# Tranzistory_jako_spina_e.net
KiCad netlist of a schematic drawn in Altium Designer
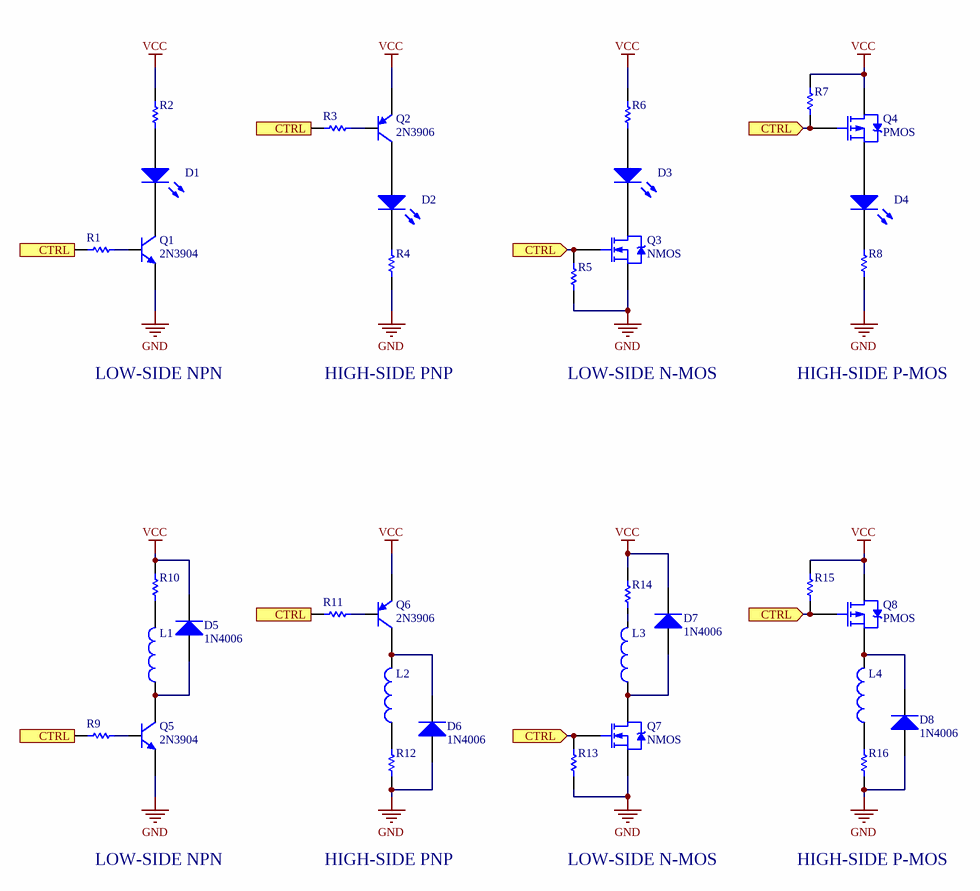
[diagram p0: Tranzistory jako spinače.SchDoc]

(export (version "E")
  (design (tool "Eeschema 10.0.6"))
  (components
    (comp (ref "D1")
      (value "LED0")
      (footprint "LED-0")
      (description "Typical INFRARED GaAs LED")
      (fields (field (name "PUBLISHER") "Altium Limited"))
      (libsource (lib "Miscellaneous Devices") (part "LED0"))
    )
    (comp (ref "D2")
      (value "LED0")
      (footprint "LED-0")
      (description "Typical INFRARED GaAs LED")
      (fields (field (name "PUBLISHER") "Altium Limited"))
      (libsource (lib "Miscellaneous Devices") (part "LED0"))
    )
    (comp (ref "D3")
      (value "LED0")
      (footprint "LED-0")
      (description "Typical INFRARED GaAs LED")
      (fields (field (name "PUBLISHER") "Altium Limited"))
      (libsource (lib "Miscellaneous Devices") (part "LED0"))
    )
    (comp (ref "D4")
      (value "LED0")
      (footprint "LED-0")
      (description "Typical INFRARED GaAs LED")
      (fields (field (name "PUBLISHER") "Altium Limited"))
      (libsource (lib "Miscellaneous Devices") (part "LED0"))
    )
    (comp (ref "D5")
      (value "1N4006")
      (footprint "DO-41")
      (description "1 Amp General Purpose Rectifier")
      (fields (field (name "PUBLISHER") "Altium Limited"))
      (libsource (lib "Miscellaneous Devices") (part "Diode 1N4006"))
    )
    (comp (ref "D6")
      (value "1N4006")
      (footprint "DO-41")
      (description "1 Amp General Purpose Rectifier")
      (fields (field (name "PUBLISHER") "Altium Limited"))
      (libsource (lib "Miscellaneous Devices") (part "Diode 1N4006"))
    )
    (comp (ref "D7")
      (value "1N4006")
      (footprint "DO-41")
      (description "1 Amp General Purpose Rectifier")
      (fields (field (name "PUBLISHER") "Altium Limited"))
      (libsource (lib "Miscellaneous Devices") (part "Diode 1N4006"))
    )
    (comp (ref "D8")
      (value "1N4006")
      (footprint "DO-41")
      (description "1 Amp General Purpose Rectifier")
      (fields (field (name "PUBLISHER") "Altium Limited"))
      (libsource (lib "Miscellaneous Devices") (part "Diode 1N4006"))
    )
    (comp (ref "L1")
      (value "Inductor")
      (footprint "0402-A")
      (fields (field (name "PUBLISHER") "Altium Limited"))
      (libsource (lib "Miscellaneous Devices") (part "Inductor"))
    )
    (comp (ref "L2")
      (value "Inductor")
      (footprint "0402-A")
      (fields (field (name "PUBLISHER") "Altium Limited"))
      (libsource (lib "Miscellaneous Devices") (part "Inductor"))
    )
    (comp (ref "L3")
      (value "Inductor")
      (footprint "0402-A")
      (fields (field (name "PUBLISHER") "Altium Limited"))
      (libsource (lib "Miscellaneous Devices") (part "Inductor"))
    )
    (comp (ref "L4")
      (value "Inductor")
      (footprint "0402-A")
      (fields (field (name "PUBLISHER") "Altium Limited"))
      (libsource (lib "Miscellaneous Devices") (part "Inductor"))
    )
    (comp (ref "Q1")
      (value "2N3904")
      (footprint "TO-92A")
      (description "NPN General Purpose Amplifier")
      (fields (field (name "PUBLISHER") "Altium Limited"))
      (libsource (lib "Miscellaneous Devices") (part "2N3904"))
    )
    (comp (ref "Q2")
      (value "2N3906")
      (footprint "TO-92A")
      (description "PNP General Purpose Amplifier")
      (fields (field (name "PUBLISHER") "Altium Limited"))
      (libsource (lib "Miscellaneous Devices") (part "2N3906"))
    )
    (comp (ref "Q3")
      (value "NMOS")
      (footprint "TO-220AB")
      (description "N-Channel Power MOSFET")
      (fields (field (name "PUBLISHER") "Altium Limited"))
      (libsource (lib "Miscellaneous Devices") (part "NMOS-2"))
    )
    (comp (ref "Q4")
      (value "PMOS")
      (footprint "TO-220AB")
      (description "P-Channel Power MOSFET")
      (fields (field (name "PUBLISHER") "Altium Limited"))
      (libsource (lib "Miscellaneous Devices") (part "PMOS-2"))
    )
    (comp (ref "Q5")
      (value "2N3904")
      (footprint "TO-92A")
      (description "NPN General Purpose Amplifier")
      (fields (field (name "PUBLISHER") "Altium Limited"))
      (libsource (lib "Miscellaneous Devices") (part "2N3904"))
    )
    (comp (ref "Q6")
      (value "2N3906")
      (footprint "TO-92A")
      (description "PNP General Purpose Amplifier")
      (fields (field (name "PUBLISHER") "Altium Limited"))
      (libsource (lib "Miscellaneous Devices") (part "2N3906"))
    )
    (comp (ref "Q7")
      (value "NMOS")
      (footprint "TO-220AB")
      (description "N-Channel Power MOSFET")
      (fields (field (name "PUBLISHER") "Altium Limited"))
      (libsource (lib "Miscellaneous Devices") (part "NMOS-2"))
    )
    (comp (ref "Q8")
      (value "PMOS")
      (footprint "TO-220AB")
      (description "P-Channel Power MOSFET")
      (fields (field (name "PUBLISHER") "Altium Limited"))
      (libsource (lib "Miscellaneous Devices") (part "PMOS-2"))
    )
    (comp (ref "R1")
      (value "Res1")
      (footprint "AXIAL-0.3")
      (description "Resistor")
      (fields (field (name "PUBLISHER") "Altium Limited"))
      (libsource (lib "Miscellaneous Devices") (part "Res1"))
    )
    (comp (ref "R2")
      (value "Res1")
      (footprint "AXIAL-0.3")
      (description "Resistor")
      (fields (field (name "PUBLISHER") "Altium Limited"))
      (libsource (lib "Miscellaneous Devices") (part "Res1"))
    )
    (comp (ref "R3")
      (value "Res1")
      (footprint "AXIAL-0.3")
      (description "Resistor")
      (fields (field (name "PUBLISHER") "Altium Limited"))
      (libsource (lib "Miscellaneous Devices") (part "Res1"))
    )
    (comp (ref "R4")
      (value "Res1")
      (footprint "AXIAL-0.3")
      (description "Resistor")
      (fields (field (name "PUBLISHER") "Altium Limited"))
      (libsource (lib "Miscellaneous Devices") (part "Res1"))
    )
    (comp (ref "R5")
      (value "Res1")
      (footprint "AXIAL-0.3")
      (description "Resistor")
      (fields (field (name "PUBLISHER") "Altium Limited"))
      (libsource (lib "Miscellaneous Devices") (part "Res1"))
    )
    (comp (ref "R6")
      (value "Res1")
      (footprint "AXIAL-0.3")
      (description "Resistor")
      (fields (field (name "PUBLISHER") "Altium Limited"))
      (libsource (lib "Miscellaneous Devices") (part "Res1"))
    )
    (comp (ref "R7")
      (value "Res1")
      (footprint "AXIAL-0.3")
      (description "Resistor")
      (fields (field (name "PUBLISHER") "Altium Limited"))
      (libsource (lib "Miscellaneous Devices") (part "Res1"))
    )
    (comp (ref "R8")
      (value "Res1")
      (footprint "AXIAL-0.3")
      (description "Resistor")
      (fields (field (name "PUBLISHER") "Altium Limited"))
      (libsource (lib "Miscellaneous Devices") (part "Res1"))
    )
    (comp (ref "R9")
      (value "Res1")
      (footprint "AXIAL-0.3")
      (description "Resistor")
      (fields (field (name "PUBLISHER") "Altium Limited"))
      (libsource (lib "Miscellaneous Devices") (part "Res1"))
    )
    (comp (ref "R10")
      (value "Res1")
      (footprint "AXIAL-0.3")
      (description "Resistor")
      (fields (field (name "PUBLISHER") "Altium Limited"))
      (libsource (lib "Miscellaneous Devices") (part "Res1"))
    )
    (comp (ref "R11")
      (value "Res1")
      (footprint "AXIAL-0.3")
      (description "Resistor")
      (fields (field (name "PUBLISHER") "Altium Limited"))
      (libsource (lib "Miscellaneous Devices") (part "Res1"))
    )
    (comp (ref "R12")
      (value "Res1")
      (footprint "AXIAL-0.3")
      (description "Resistor")
      (fields (field (name "PUBLISHER") "Altium Limited"))
      (libsource (lib "Miscellaneous Devices") (part "Res1"))
    )
    (comp (ref "R13")
      (value "Res1")
      (footprint "AXIAL-0.3")
      (description "Resistor")
      (fields (field (name "PUBLISHER") "Altium Limited"))
      (libsource (lib "Miscellaneous Devices") (part "Res1"))
    )
    (comp (ref "R14")
      (value "Res1")
      (footprint "AXIAL-0.3")
      (description "Resistor")
      (fields (field (name "PUBLISHER") "Altium Limited"))
      (libsource (lib "Miscellaneous Devices") (part "Res1"))
    )
    (comp (ref "R15")
      (value "Res1")
      (footprint "AXIAL-0.3")
      (description "Resistor")
      (fields (field (name "PUBLISHER") "Altium Limited"))
      (libsource (lib "Miscellaneous Devices") (part "Res1"))
    )
    (comp (ref "R16")
      (value "Res1")
      (footprint "AXIAL-0.3")
      (description "Resistor")
      (fields (field (name "PUBLISHER") "Altium Limited"))
      (libsource (lib "Miscellaneous Devices") (part "Res1"))
    )
  )
  (nets
    (net (code "1") (name "/CTRL") (class "Default")
      (node (ref "Q3") (pin "1") (pinfunction "G_1") (pintype "passive"))
      (node (ref "Q4") (pin "1") (pinfunction "G_1") (pintype "passive"))
      (node (ref "Q7") (pin "1") (pinfunction "G_1") (pintype "passive"))
      (node (ref "Q8") (pin "1") (pinfunction "G_1") (pintype "passive"))
      (node (ref "R1") (pin "2") (pinfunction "2_2") (pintype "passive"))
      (node (ref "R11") (pin "2") (pinfunction "2_2") (pintype "passive"))
      (node (ref "R13") (pin "1") (pinfunction "1_1") (pintype "passive"))
      (node (ref "R15") (pin "2") (pinfunction "2_2") (pintype "passive"))
      (node (ref "R3") (pin "2") (pinfunction "2_2") (pintype "passive"))
      (node (ref "R5") (pin "1") (pinfunction "1_1") (pintype "passive"))
      (node (ref "R7") (pin "2") (pinfunction "2_2") (pintype "passive"))
      (node (ref "R9") (pin "2") (pinfunction "2_2") (pintype "passive"))
    )
    (net (code "2") (name "GND") (class "Default")
      (node (ref "D6") (pin "1") (pinfunction "A_1") (pintype "passive"))
      (node (ref "D8") (pin "1") (pinfunction "A_1") (pintype "passive"))
      (node (ref "Q1") (pin "1") (pinfunction "E_1") (pintype "passive"))
      (node (ref "Q3") (pin "3") (pinfunction "S_3") (pintype "passive"))
      (node (ref "Q5") (pin "1") (pinfunction "E_1") (pintype "passive"))
      (node (ref "Q7") (pin "3") (pinfunction "S_3") (pintype "passive"))
      (node (ref "R12") (pin "1") (pinfunction "1_1") (pintype "passive"))
      (node (ref "R13") (pin "2") (pinfunction "2_2") (pintype "passive"))
      (node (ref "R16") (pin "1") (pinfunction "1_1") (pintype "passive"))
      (node (ref "R4") (pin "1") (pinfunction "1_1") (pintype "passive"))
      (node (ref "R5") (pin "2") (pinfunction "2_2") (pintype "passive"))
      (node (ref "R8") (pin "1") (pinfunction "1_1") (pintype "passive"))
    )
    (net (code "3") (name "Net-(D1-A)") (class "Default")
      (node (ref "D1") (pin "1") (pinfunction "A_1") (pintype "passive"))
      (node (ref "R2") (pin "1") (pinfunction "1_1") (pintype "passive"))
    )
    (net (code "4") (name "Net-(D1-K)") (class "Default")
      (node (ref "D1") (pin "2") (pinfunction "K_2") (pintype "passive"))
      (node (ref "Q1") (pin "3") (pinfunction "C_3") (pintype "passive"))
    )
    (net (code "5") (name "Net-(D2-A)") (class "Default")
      (node (ref "D2") (pin "1") (pinfunction "A_1") (pintype "passive"))
      (node (ref "Q2") (pin "3") (pinfunction "C_3") (pintype "passive"))
    )
    (net (code "6") (name "Net-(D2-K)") (class "Default")
      (node (ref "D2") (pin "2") (pinfunction "K_2") (pintype "passive"))
      (node (ref "R4") (pin "2") (pinfunction "2_2") (pintype "passive"))
    )
    (net (code "7") (name "Net-(D3-A)") (class "Default")
      (node (ref "D3") (pin "1") (pinfunction "A_1") (pintype "passive"))
      (node (ref "R6") (pin "1") (pinfunction "1_1") (pintype "passive"))
    )
    (net (code "8") (name "Net-(D3-K)") (class "Default")
      (node (ref "D3") (pin "2") (pinfunction "K_2") (pintype "passive"))
      (node (ref "Q3") (pin "2") (pinfunction "D_2") (pintype "passive"))
    )
    (net (code "9") (name "Net-(D4-A)") (class "Default")
      (node (ref "D4") (pin "1") (pinfunction "A_1") (pintype "passive"))
      (node (ref "Q4") (pin "3") (pinfunction "S_3") (pintype "passive"))
    )
    (net (code "10") (name "Net-(D4-K)") (class "Default")
      (node (ref "D4") (pin "2") (pinfunction "K_2") (pintype "passive"))
      (node (ref "R8") (pin "2") (pinfunction "2_2") (pintype "passive"))
    )
    (net (code "11") (name "Net-(D5-A)") (class "Default")
      (node (ref "D5") (pin "1") (pinfunction "A_1") (pintype "passive"))
      (node (ref "L1") (pin "1") (pinfunction "1_1") (pintype "passive"))
      (node (ref "Q5") (pin "3") (pinfunction "C_3") (pintype "passive"))
    )
    (net (code "12") (name "Net-(D6-K)") (class "Default")
      (node (ref "D6") (pin "2") (pinfunction "K_2") (pintype "passive"))
      (node (ref "L2") (pin "2") (pinfunction "2_2") (pintype "passive"))
      (node (ref "Q6") (pin "3") (pinfunction "C_3") (pintype "passive"))
    )
    (net (code "13") (name "Net-(D7-A)") (class "Default")
      (node (ref "D7") (pin "1") (pinfunction "A_1") (pintype "passive"))
      (node (ref "L3") (pin "1") (pinfunction "1_1") (pintype "passive"))
      (node (ref "Q7") (pin "2") (pinfunction "D_2") (pintype "passive"))
    )
    (net (code "14") (name "Net-(D8-K)") (class "Default")
      (node (ref "D8") (pin "2") (pinfunction "K_2") (pintype "passive"))
      (node (ref "L4") (pin "2") (pinfunction "2_2") (pintype "passive"))
      (node (ref "Q8") (pin "3") (pinfunction "S_3") (pintype "passive"))
    )
    (net (code "15") (name "Net-(L1-Pad2)") (class "Default")
      (node (ref "L1") (pin "2") (pinfunction "2_2") (pintype "passive"))
      (node (ref "R10") (pin "1") (pinfunction "1_1") (pintype "passive"))
    )
    (net (code "16") (name "Net-(L2-Pad1)") (class "Default")
      (node (ref "L2") (pin "1") (pinfunction "1_1") (pintype "passive"))
      (node (ref "R12") (pin "2") (pinfunction "2_2") (pintype "passive"))
    )
    (net (code "17") (name "Net-(L3-Pad2)") (class "Default")
      (node (ref "L3") (pin "2") (pinfunction "2_2") (pintype "passive"))
      (node (ref "R14") (pin "1") (pinfunction "1_1") (pintype "passive"))
    )
    (net (code "18") (name "Net-(L4-Pad1)") (class "Default")
      (node (ref "L4") (pin "1") (pinfunction "1_1") (pintype "passive"))
      (node (ref "R16") (pin "2") (pinfunction "2_2") (pintype "passive"))
    )
    (net (code "19") (name "Net-(Q1-B)") (class "Default")
      (node (ref "Q1") (pin "2") (pinfunction "B_2") (pintype "passive"))
      (node (ref "R1") (pin "1") (pinfunction "1_1") (pintype "passive"))
    )
    (net (code "20") (name "Net-(Q2-B)") (class "Default")
      (node (ref "Q2") (pin "2") (pinfunction "B_2") (pintype "passive"))
      (node (ref "R3") (pin "1") (pinfunction "1_1") (pintype "passive"))
    )
    (net (code "21") (name "Net-(Q5-B)") (class "Default")
      (node (ref "Q5") (pin "2") (pinfunction "B_2") (pintype "passive"))
      (node (ref "R9") (pin "1") (pinfunction "1_1") (pintype "passive"))
    )
    (net (code "22") (name "Net-(Q6-B)") (class "Default")
      (node (ref "Q6") (pin "2") (pinfunction "B_2") (pintype "passive"))
      (node (ref "R11") (pin "1") (pinfunction "1_1") (pintype "passive"))
    )
    (net (code "23") (name "VCC") (class "Default")
      (node (ref "D5") (pin "2") (pinfunction "K_2") (pintype "passive"))
      (node (ref "D7") (pin "2") (pinfunction "K_2") (pintype "passive"))
      (node (ref "Q2") (pin "1") (pinfunction "E_1") (pintype "passive"))
      (node (ref "Q4") (pin "2") (pinfunction "D_2") (pintype "passive"))
      (node (ref "Q6") (pin "1") (pinfunction "E_1") (pintype "passive"))
      (node (ref "Q8") (pin "2") (pinfunction "D_2") (pintype "passive"))
      (node (ref "R10") (pin "2") (pinfunction "2_2") (pintype "passive"))
      (node (ref "R14") (pin "2") (pinfunction "2_2") (pintype "passive"))
      (node (ref "R15") (pin "1") (pinfunction "1_1") (pintype "passive"))
      (node (ref "R2") (pin "2") (pinfunction "2_2") (pintype "passive"))
      (node (ref "R6") (pin "2") (pinfunction "2_2") (pintype "passive"))
      (node (ref "R7") (pin "1") (pinfunction "1_1") (pintype "passive"))
    )
  )
)
